# B5_EM_-Z_SOLAR_PANEL.net
KiCad netlist of a schematic drawn in EAGLE
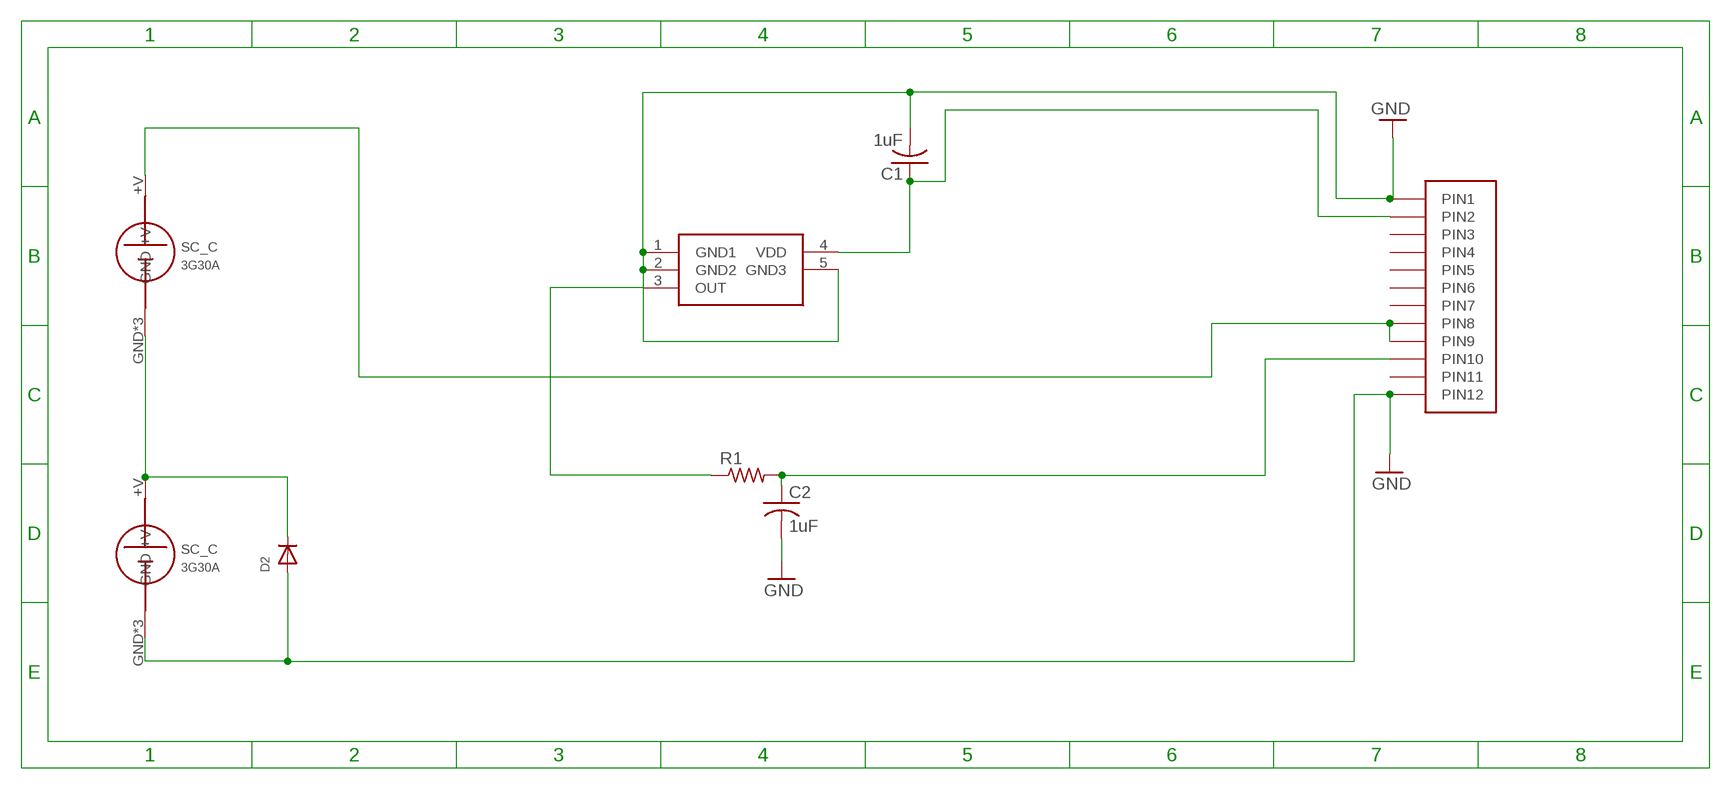
[diagram p0: schematic, sheet 1]

(export (version "E")
  (design (tool "Eeschema 10.0.6"))
  (components
    (comp (ref "C1")
      (value "1uF")
      (footprint "eagle-import:C0805")
      (libsource (lib "eagle-import") (part "C-USC0805"))
    )
    (comp (ref "C2")
      (value "1uF")
      (footprint "eagle-import:C0805")
      (libsource (lib "eagle-import") (part "C-USC0805"))
    )
    (comp (ref "D2")
      (value "DIODE_SOD-123FL")
      (footprint "eagle-import:SOD-123FL")
      (libsource (lib "eagle-import") (part "DIODE_SOD-123FL"))
    )
    (comp (ref "R1")
      (value "R-US_R0402")
      (footprint "eagle-import:R0402")
      (libsource (lib "eagle-import") (part "R-US_R0402"))
    )
    (comp (ref "U$1")
      (value "HEADER12PIN")
      (footprint "eagle-import:HEADER12PIN")
      (libsource (lib "eagle-import") (part "HEADER12PIN"))
    )
    (comp (ref "U$3")
      (value "LMT84DCKT")
      (footprint "eagle-import:SOT65P210X110-5N")
      (fields (field (name "RS_PART_NUMBER") "8115860"))
      (libsource (lib "eagle-import") (part "LMT84DCKT"))
    )
    (comp (ref "U$4")
      (value "SC_C")
      (footprint "eagle-import:SC_C")
      (libsource (lib "eagle-import") (part "SC_C"))
    )
    (comp (ref "U$5")
      (value "SC_C")
      (footprint "eagle-import:SC_C")
      (libsource (lib "eagle-import") (part "SC_C"))
    )
  )
  (nets
    (net (code "1") (name "GND") (class "Default")
      (node (ref "C1") (pin "2") (pinfunction "2_2") (pintype "passive"))
      (node (ref "C2") (pin "2") (pinfunction "2_2") (pintype "passive"))
      (node (ref "D2") (pin "A") (pinfunction "A_A") (pintype "passive"))
      (node (ref "U$1") (pin "P1") (pinfunction "PIN1_P1") (pintype "bidirectional"))
      (node (ref "U$1") (pin "P12") (pinfunction "PIN12_P12") (pintype "bidirectional"))
      (node (ref "U$3") (pin "1") (pinfunction "GND1_1") (pintype "power_in"))
      (node (ref "U$3") (pin "2") (pinfunction "GND2_2") (pintype "power_in"))
      (node (ref "U$3") (pin "5") (pinfunction "GND3_5") (pintype "power_in"))
      (node (ref "U$4") (pin "GND") (pinfunction "GND_GND") (pintype "bidirectional"))
      (node (ref "U$4") (pin "GND1") (pinfunction "GND_GND1") (pintype "bidirectional"))
      (node (ref "U$4") (pin "GND2") (pinfunction "GND_GND2") (pintype "bidirectional"))
    )
    (net (code "2") (name "Net-(D2-PadC)") (class "Default")
      (node (ref "D2") (pin "C") (pinfunction "C_C") (pintype "passive"))
      (node (ref "U$4") (pin "+V") (pinfunction "+V_+V") (pintype "bidirectional"))
      (node (ref "U$5") (pin "GND") (pinfunction "GND_GND") (pintype "bidirectional"))
      (node (ref "U$5") (pin "GND1") (pinfunction "GND_GND1") (pintype "bidirectional"))
      (node (ref "U$5") (pin "GND2") (pinfunction "GND_GND2") (pintype "bidirectional"))
    )
    (net (code "3") (name "Net-(U$1-PIN2)") (class "Default")
      (node (ref "C1") (pin "1") (pinfunction "1_1") (pintype "passive"))
      (node (ref "U$1") (pin "P2") (pinfunction "PIN2_P2") (pintype "bidirectional"))
      (node (ref "U$3") (pin "4") (pinfunction "VDD_4") (pintype "power_in"))
    )
    (net (code "4") (name "Net-(U$1-PIN8)") (class "Default")
      (node (ref "U$1") (pin "P8") (pinfunction "PIN8_P8") (pintype "bidirectional"))
      (node (ref "U$1") (pin "P9") (pinfunction "PIN9_P9") (pintype "bidirectional"))
      (node (ref "U$5") (pin "+V") (pinfunction "+V_+V") (pintype "bidirectional"))
    )
    (net (code "5") (name "Net-(U$1-PIN10)") (class "Default")
      (node (ref "C2") (pin "1") (pinfunction "1_1") (pintype "passive"))
      (node (ref "R1") (pin "2") (pinfunction "2_2") (pintype "passive"))
      (node (ref "U$1") (pin "P10") (pinfunction "PIN10_P10") (pintype "bidirectional"))
    )
    (net (code "6") (name "Net-(U$3-OUT)") (class "Default")
      (node (ref "R1") (pin "1") (pinfunction "1_1") (pintype "passive"))
      (node (ref "U$3") (pin "3") (pinfunction "OUT_3") (pintype "output"))
    )
    (net (code "7") (name "unconnected-(U$1-PIN3-PadP3)") (class "Default")
      (node (ref "U$1") (pin "P3") (pinfunction "PIN3_P3") (pintype "bidirectional"))
    )
    (net (code "8") (name "unconnected-(U$1-PIN4-PadP4)") (class "Default")
      (node (ref "U$1") (pin "P4") (pinfunction "PIN4_P4") (pintype "bidirectional"))
    )
    (net (code "9") (name "unconnected-(U$1-PIN5-PadP5)") (class "Default")
      (node (ref "U$1") (pin "P5") (pinfunction "PIN5_P5") (pintype "bidirectional"))
    )
    (net (code "10") (name "unconnected-(U$1-PIN6-PadP6)") (class "Default")
      (node (ref "U$1") (pin "P6") (pinfunction "PIN6_P6") (pintype "bidirectional"))
    )
    (net (code "11") (name "unconnected-(U$1-PIN7-PadP7)") (class "Default")
      (node (ref "U$1") (pin "P7") (pinfunction "PIN7_P7") (pintype "bidirectional"))
    )
    (net (code "12") (name "unconnected-(U$1-PIN11-PadP11)") (class "Default")
      (node (ref "U$1") (pin "P11") (pinfunction "PIN11_P11") (pintype "bidirectional"))
    )
  )
)
